# SubBus2.net
KiCad netlist of a schematic drawn in Altium Designer
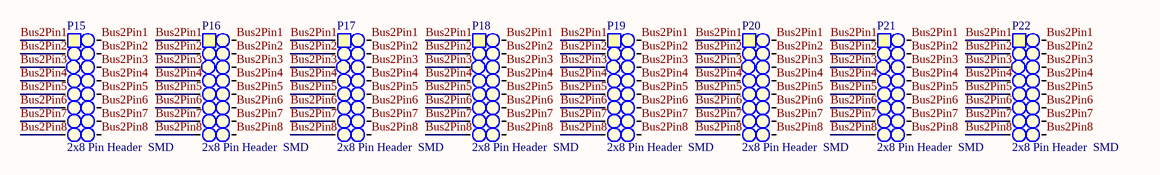
[diagram p0: SubBus2.SchDoc]

(export (version "E")
  (design (tool "Eeschema 10.0.6"))
  (components
    (comp (ref "P15")
      (value "2x8 Pin Header  SMD")
      (footprint "2X8_SMD_PH_2.54")
      (description "2.54mm, SMD")
      (libsource (lib "jclib") (part "2x8 Pin Header  SMD"))
    )
    (comp (ref "P16")
      (value "2x8 Pin Header  SMD")
      (footprint "2X8_SMD_PH_2.54")
      (description "2.54mm, SMD")
      (libsource (lib "jclib") (part "2x8 Pin Header  SMD"))
    )
    (comp (ref "P17")
      (value "2x8 Pin Header  SMD")
      (footprint "2X8_SMD_PH_2.54")
      (description "2.54mm, SMD")
      (libsource (lib "jclib") (part "2x8 Pin Header  SMD"))
    )
    (comp (ref "P18")
      (value "2x8 Pin Header  SMD")
      (footprint "2X8_SMD_PH_2.54")
      (description "2.54mm, SMD")
      (libsource (lib "jclib") (part "2x8 Pin Header  SMD"))
    )
    (comp (ref "P19")
      (value "2x8 Pin Header  SMD")
      (footprint "2X8_SMD_PH_2.54")
      (description "2.54mm, SMD")
      (libsource (lib "jclib") (part "2x8 Pin Header  SMD"))
    )
    (comp (ref "P20")
      (value "2x8 Pin Header  SMD")
      (footprint "2X8_SMD_PH_2.54")
      (description "2.54mm, SMD")
      (libsource (lib "jclib") (part "2x8 Pin Header  SMD"))
    )
    (comp (ref "P21")
      (value "2x8 Pin Header  SMD")
      (footprint "2X8_SMD_PH_2.54")
      (description "2.54mm, SMD")
      (libsource (lib "jclib") (part "2x8 Pin Header  SMD"))
    )
    (comp (ref "P22")
      (value "2x8 Pin Header  SMD")
      (footprint "2X8_SMD_PH_2.54")
      (description "2.54mm, SMD")
      (libsource (lib "jclib") (part "2x8 Pin Header  SMD"))
    )
  )
  (nets
    (net (code "1") (name "/Bus2Pin1") (class "Default")
      (node (ref "P15") (pin "1") (pinfunction "1_1") (pintype "passive"))
      (node (ref "P15") (pin "16") (pinfunction "16_16") (pintype "passive"))
      (node (ref "P16") (pin "1") (pinfunction "1_1") (pintype "passive"))
      (node (ref "P16") (pin "16") (pinfunction "16_16") (pintype "passive"))
      (node (ref "P17") (pin "1") (pinfunction "1_1") (pintype "passive"))
      (node (ref "P17") (pin "16") (pinfunction "16_16") (pintype "passive"))
      (node (ref "P18") (pin "1") (pinfunction "1_1") (pintype "passive"))
      (node (ref "P18") (pin "16") (pinfunction "16_16") (pintype "passive"))
      (node (ref "P19") (pin "1") (pinfunction "1_1") (pintype "passive"))
      (node (ref "P19") (pin "16") (pinfunction "16_16") (pintype "passive"))
      (node (ref "P20") (pin "1") (pinfunction "1_1") (pintype "passive"))
      (node (ref "P20") (pin "16") (pinfunction "16_16") (pintype "passive"))
      (node (ref "P21") (pin "1") (pinfunction "1_1") (pintype "passive"))
      (node (ref "P21") (pin "16") (pinfunction "16_16") (pintype "passive"))
      (node (ref "P22") (pin "1") (pinfunction "1_1") (pintype "passive"))
      (node (ref "P22") (pin "16") (pinfunction "16_16") (pintype "passive"))
    )
    (net (code "2") (name "/Bus2Pin2") (class "Default")
      (node (ref "P15") (pin "15") (pinfunction "15_15") (pintype "passive"))
      (node (ref "P15") (pin "2") (pinfunction "2_2") (pintype "passive"))
      (node (ref "P16") (pin "15") (pinfunction "15_15") (pintype "passive"))
      (node (ref "P16") (pin "2") (pinfunction "2_2") (pintype "passive"))
      (node (ref "P17") (pin "15") (pinfunction "15_15") (pintype "passive"))
      (node (ref "P17") (pin "2") (pinfunction "2_2") (pintype "passive"))
      (node (ref "P18") (pin "15") (pinfunction "15_15") (pintype "passive"))
      (node (ref "P18") (pin "2") (pinfunction "2_2") (pintype "passive"))
      (node (ref "P19") (pin "15") (pinfunction "15_15") (pintype "passive"))
      (node (ref "P19") (pin "2") (pinfunction "2_2") (pintype "passive"))
      (node (ref "P20") (pin "15") (pinfunction "15_15") (pintype "passive"))
      (node (ref "P20") (pin "2") (pinfunction "2_2") (pintype "passive"))
      (node (ref "P21") (pin "15") (pinfunction "15_15") (pintype "passive"))
      (node (ref "P21") (pin "2") (pinfunction "2_2") (pintype "passive"))
      (node (ref "P22") (pin "15") (pinfunction "15_15") (pintype "passive"))
      (node (ref "P22") (pin "2") (pinfunction "2_2") (pintype "passive"))
    )
    (net (code "3") (name "/Bus2Pin3") (class "Default")
      (node (ref "P15") (pin "14") (pinfunction "14_14") (pintype "passive"))
      (node (ref "P15") (pin "3") (pinfunction "3_3") (pintype "passive"))
      (node (ref "P16") (pin "14") (pinfunction "14_14") (pintype "passive"))
      (node (ref "P16") (pin "3") (pinfunction "3_3") (pintype "passive"))
      (node (ref "P17") (pin "14") (pinfunction "14_14") (pintype "passive"))
      (node (ref "P17") (pin "3") (pinfunction "3_3") (pintype "passive"))
      (node (ref "P18") (pin "14") (pinfunction "14_14") (pintype "passive"))
      (node (ref "P18") (pin "3") (pinfunction "3_3") (pintype "passive"))
      (node (ref "P19") (pin "14") (pinfunction "14_14") (pintype "passive"))
      (node (ref "P19") (pin "3") (pinfunction "3_3") (pintype "passive"))
      (node (ref "P20") (pin "14") (pinfunction "14_14") (pintype "passive"))
      (node (ref "P20") (pin "3") (pinfunction "3_3") (pintype "passive"))
      (node (ref "P21") (pin "14") (pinfunction "14_14") (pintype "passive"))
      (node (ref "P21") (pin "3") (pinfunction "3_3") (pintype "passive"))
      (node (ref "P22") (pin "14") (pinfunction "14_14") (pintype "passive"))
      (node (ref "P22") (pin "3") (pinfunction "3_3") (pintype "passive"))
    )
    (net (code "4") (name "/Bus2Pin4") (class "Default")
      (node (ref "P15") (pin "13") (pinfunction "13_13") (pintype "passive"))
      (node (ref "P15") (pin "4") (pinfunction "4_4") (pintype "passive"))
      (node (ref "P16") (pin "13") (pinfunction "13_13") (pintype "passive"))
      (node (ref "P16") (pin "4") (pinfunction "4_4") (pintype "passive"))
      (node (ref "P17") (pin "13") (pinfunction "13_13") (pintype "passive"))
      (node (ref "P17") (pin "4") (pinfunction "4_4") (pintype "passive"))
      (node (ref "P18") (pin "13") (pinfunction "13_13") (pintype "passive"))
      (node (ref "P18") (pin "4") (pinfunction "4_4") (pintype "passive"))
      (node (ref "P19") (pin "13") (pinfunction "13_13") (pintype "passive"))
      (node (ref "P19") (pin "4") (pinfunction "4_4") (pintype "passive"))
      (node (ref "P20") (pin "13") (pinfunction "13_13") (pintype "passive"))
      (node (ref "P20") (pin "4") (pinfunction "4_4") (pintype "passive"))
      (node (ref "P21") (pin "13") (pinfunction "13_13") (pintype "passive"))
      (node (ref "P21") (pin "4") (pinfunction "4_4") (pintype "passive"))
      (node (ref "P22") (pin "13") (pinfunction "13_13") (pintype "passive"))
      (node (ref "P22") (pin "4") (pinfunction "4_4") (pintype "passive"))
    )
    (net (code "5") (name "/Bus2Pin5") (class "Default")
      (node (ref "P15") (pin "12") (pinfunction "12_12") (pintype "passive"))
      (node (ref "P15") (pin "5") (pinfunction "5_5") (pintype "passive"))
      (node (ref "P16") (pin "12") (pinfunction "12_12") (pintype "passive"))
      (node (ref "P16") (pin "5") (pinfunction "5_5") (pintype "passive"))
      (node (ref "P17") (pin "12") (pinfunction "12_12") (pintype "passive"))
      (node (ref "P17") (pin "5") (pinfunction "5_5") (pintype "passive"))
      (node (ref "P18") (pin "12") (pinfunction "12_12") (pintype "passive"))
      (node (ref "P18") (pin "5") (pinfunction "5_5") (pintype "passive"))
      (node (ref "P19") (pin "12") (pinfunction "12_12") (pintype "passive"))
      (node (ref "P19") (pin "5") (pinfunction "5_5") (pintype "passive"))
      (node (ref "P20") (pin "12") (pinfunction "12_12") (pintype "passive"))
      (node (ref "P20") (pin "5") (pinfunction "5_5") (pintype "passive"))
      (node (ref "P21") (pin "12") (pinfunction "12_12") (pintype "passive"))
      (node (ref "P21") (pin "5") (pinfunction "5_5") (pintype "passive"))
      (node (ref "P22") (pin "12") (pinfunction "12_12") (pintype "passive"))
      (node (ref "P22") (pin "5") (pinfunction "5_5") (pintype "passive"))
    )
    (net (code "6") (name "/Bus2Pin6") (class "Default")
      (node (ref "P15") (pin "11") (pinfunction "11_11") (pintype "passive"))
      (node (ref "P15") (pin "6") (pinfunction "6_6") (pintype "passive"))
      (node (ref "P16") (pin "11") (pinfunction "11_11") (pintype "passive"))
      (node (ref "P16") (pin "6") (pinfunction "6_6") (pintype "passive"))
      (node (ref "P17") (pin "11") (pinfunction "11_11") (pintype "passive"))
      (node (ref "P17") (pin "6") (pinfunction "6_6") (pintype "passive"))
      (node (ref "P18") (pin "11") (pinfunction "11_11") (pintype "passive"))
      (node (ref "P18") (pin "6") (pinfunction "6_6") (pintype "passive"))
      (node (ref "P19") (pin "11") (pinfunction "11_11") (pintype "passive"))
      (node (ref "P19") (pin "6") (pinfunction "6_6") (pintype "passive"))
      (node (ref "P20") (pin "11") (pinfunction "11_11") (pintype "passive"))
      (node (ref "P20") (pin "6") (pinfunction "6_6") (pintype "passive"))
      (node (ref "P21") (pin "11") (pinfunction "11_11") (pintype "passive"))
      (node (ref "P21") (pin "6") (pinfunction "6_6") (pintype "passive"))
      (node (ref "P22") (pin "11") (pinfunction "11_11") (pintype "passive"))
      (node (ref "P22") (pin "6") (pinfunction "6_6") (pintype "passive"))
    )
    (net (code "7") (name "/Bus2Pin7") (class "Default")
      (node (ref "P15") (pin "10") (pinfunction "10_10") (pintype "passive"))
      (node (ref "P15") (pin "7") (pinfunction "7_7") (pintype "passive"))
      (node (ref "P16") (pin "10") (pinfunction "10_10") (pintype "passive"))
      (node (ref "P16") (pin "7") (pinfunction "7_7") (pintype "passive"))
      (node (ref "P17") (pin "10") (pinfunction "10_10") (pintype "passive"))
      (node (ref "P17") (pin "7") (pinfunction "7_7") (pintype "passive"))
      (node (ref "P18") (pin "10") (pinfunction "10_10") (pintype "passive"))
      (node (ref "P18") (pin "7") (pinfunction "7_7") (pintype "passive"))
      (node (ref "P19") (pin "10") (pinfunction "10_10") (pintype "passive"))
      (node (ref "P19") (pin "7") (pinfunction "7_7") (pintype "passive"))
      (node (ref "P20") (pin "10") (pinfunction "10_10") (pintype "passive"))
      (node (ref "P20") (pin "7") (pinfunction "7_7") (pintype "passive"))
      (node (ref "P21") (pin "10") (pinfunction "10_10") (pintype "passive"))
      (node (ref "P21") (pin "7") (pinfunction "7_7") (pintype "passive"))
      (node (ref "P22") (pin "10") (pinfunction "10_10") (pintype "passive"))
      (node (ref "P22") (pin "7") (pinfunction "7_7") (pintype "passive"))
    )
    (net (code "8") (name "/Bus2Pin8") (class "Default")
      (node (ref "P15") (pin "8") (pinfunction "8_8") (pintype "passive"))
      (node (ref "P15") (pin "9") (pinfunction "9_9") (pintype "passive"))
      (node (ref "P16") (pin "8") (pinfunction "8_8") (pintype "passive"))
      (node (ref "P16") (pin "9") (pinfunction "9_9") (pintype "passive"))
      (node (ref "P17") (pin "8") (pinfunction "8_8") (pintype "passive"))
      (node (ref "P17") (pin "9") (pinfunction "9_9") (pintype "passive"))
      (node (ref "P18") (pin "8") (pinfunction "8_8") (pintype "passive"))
      (node (ref "P18") (pin "9") (pinfunction "9_9") (pintype "passive"))
      (node (ref "P19") (pin "8") (pinfunction "8_8") (pintype "passive"))
      (node (ref "P19") (pin "9") (pinfunction "9_9") (pintype "passive"))
      (node (ref "P20") (pin "8") (pinfunction "8_8") (pintype "passive"))
      (node (ref "P20") (pin "9") (pinfunction "9_9") (pintype "passive"))
      (node (ref "P21") (pin "8") (pinfunction "8_8") (pintype "passive"))
      (node (ref "P21") (pin "9") (pinfunction "9_9") (pintype "passive"))
      (node (ref "P22") (pin "8") (pinfunction "8_8") (pintype "passive"))
      (node (ref "P22") (pin "9") (pinfunction "9_9") (pintype "passive"))
    )
  )
)
